# Charger.net
KiCad netlist of a schematic drawn in Altium Designer
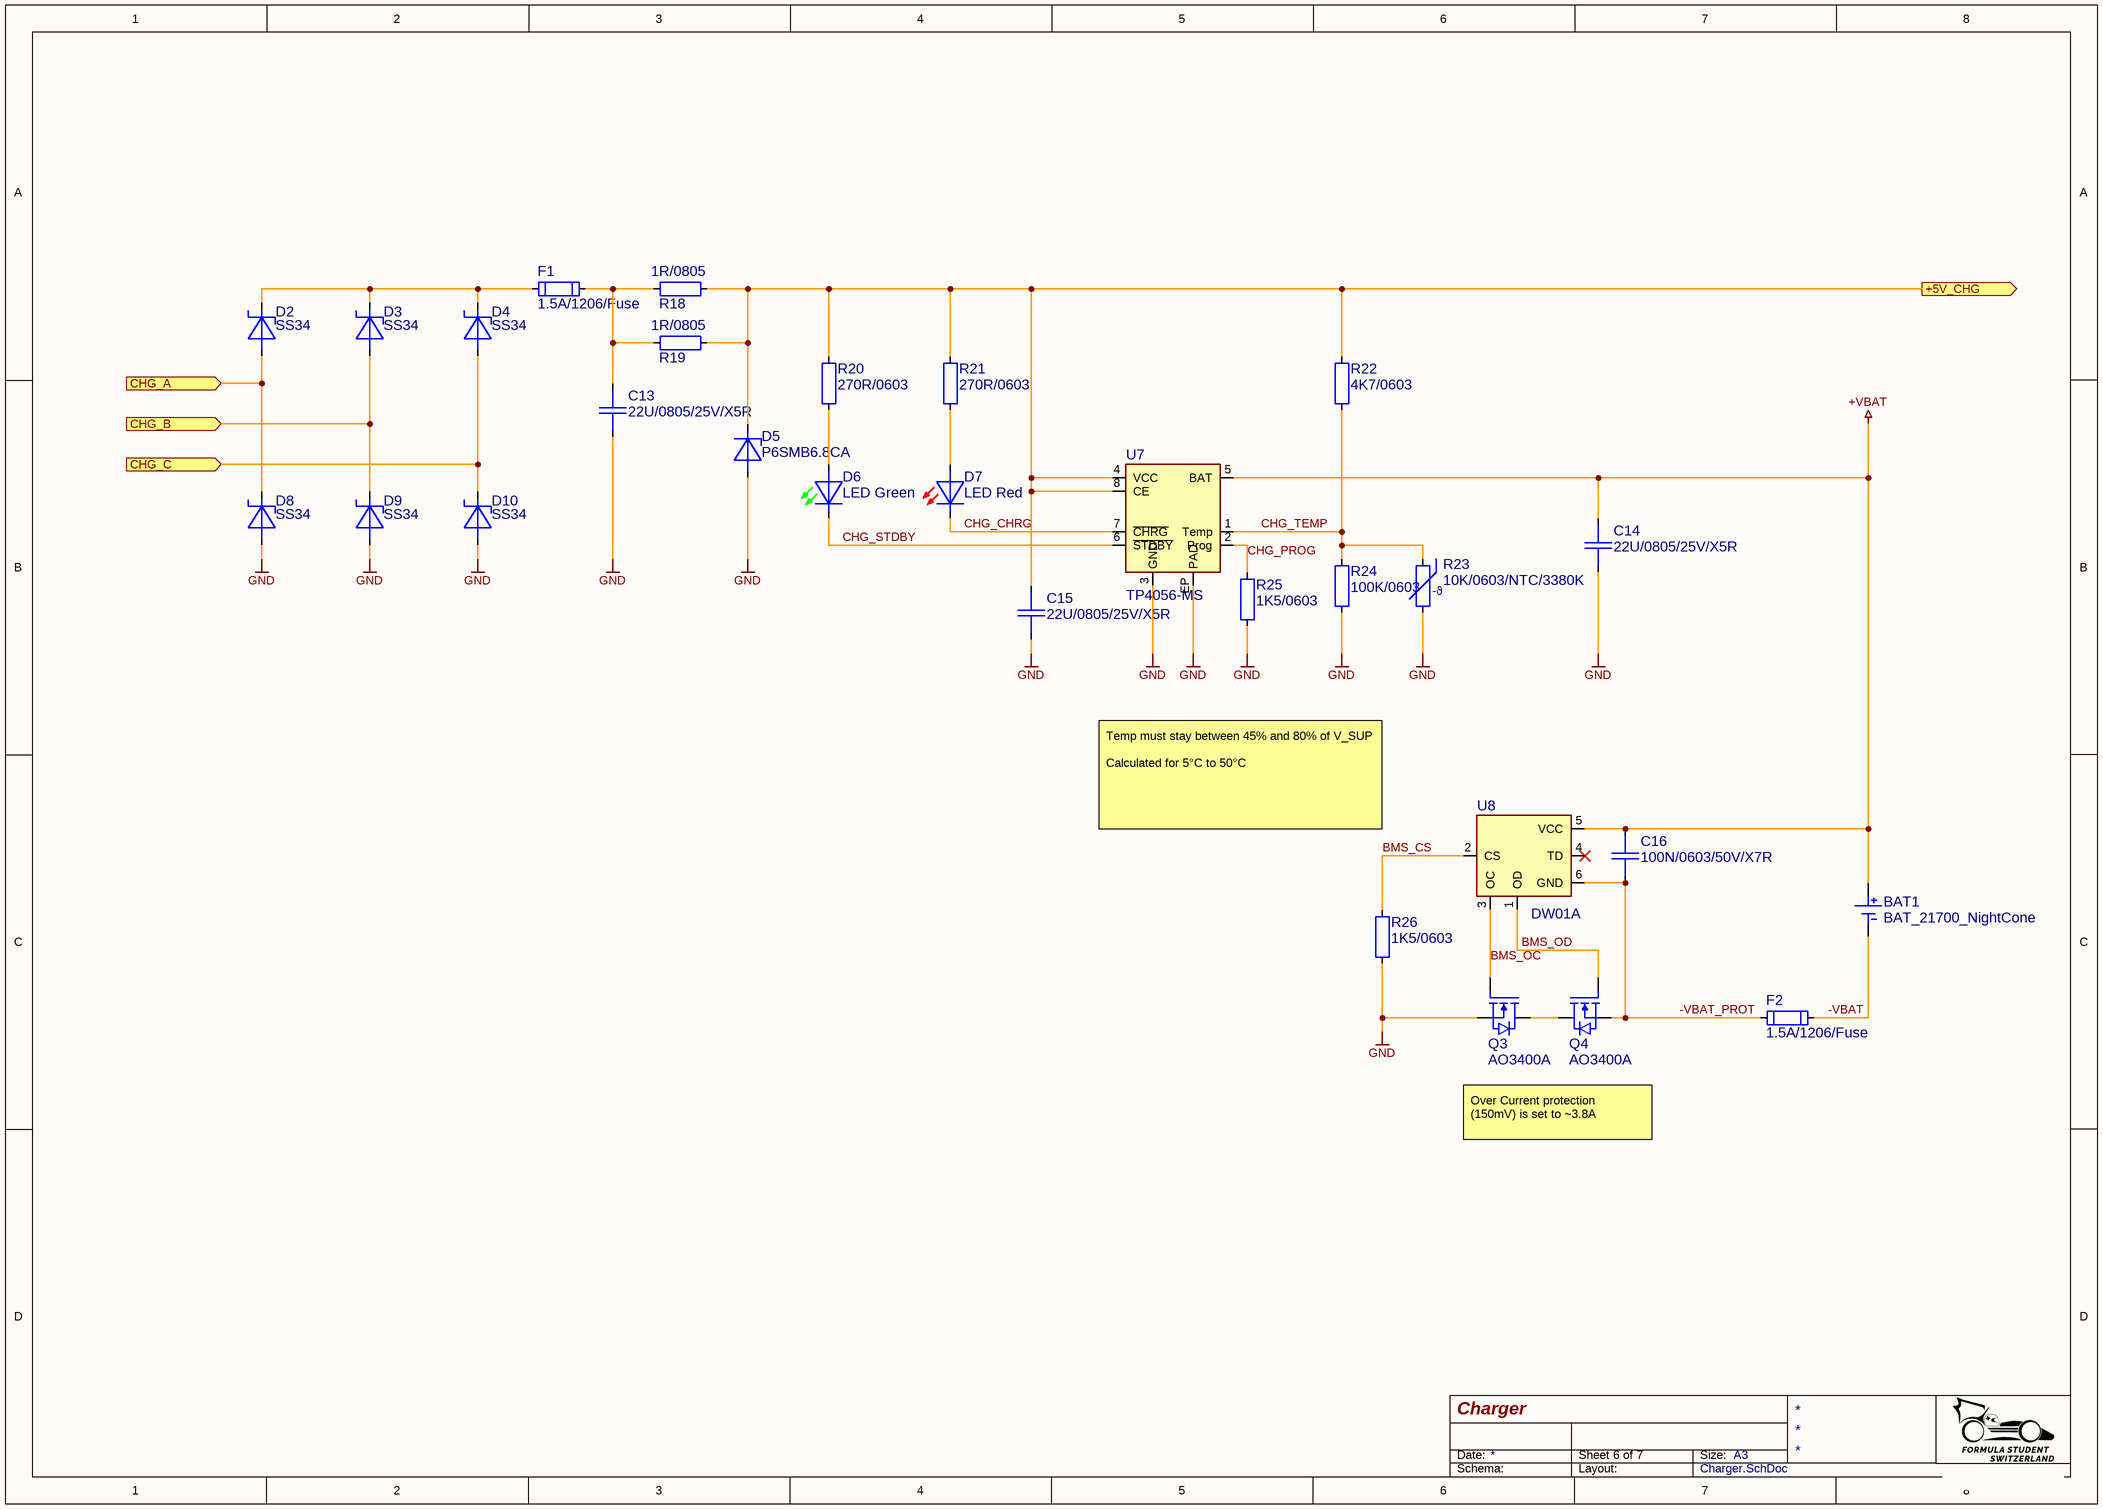
[diagram p0: Charger.SchDoc]

(export (version "E")
  (design (tool "Eeschema 10.0.6"))
  (components
    (comp (ref "BAT1")
      (value "BAT_21700_NightCone")
      (footprint "BAT-21700-NC")
      (description "21700 Battery cell for FSCH nightcone project")
      (fields (field (name "MANUFACTURER") "NONE"))
      (libsource (lib "daniw_altium_lib") (part "Battery_1"))
    )
    (comp (ref "C13")
      (value "22U/0805/25V/X5R")
      (footprint "CAP0805_X7R")
      (description "CAP SM 0805 22uF 25V X5R")
      (fields (field (name "MANUFACTURER") "GENERIC"))
      (libsource (lib "daniw_altium_lib") (part "C"))
    )
    (comp (ref "C14")
      (value "22U/0805/25V/X5R")
      (footprint "CAP0805_X7R")
      (description "CAP SM 0805 22uF 25V X5R")
      (fields (field (name "MANUFACTURER") "GENERIC"))
      (libsource (lib "daniw_altium_lib") (part "C"))
    )
    (comp (ref "C15")
      (value "22U/0805/25V/X5R")
      (footprint "CAP0805_X7R")
      (description "CAP SM 0805 22uF 25V X5R")
      (fields (field (name "MANUFACTURER") "GENERIC"))
      (libsource (lib "daniw_altium_lib") (part "C"))
    )
    (comp (ref "C16")
      (value "100N/0603/50V/X7R")
      (footprint "CAP0603_X7R")
      (description "CAP SM 0603 100nF 50V X7R")
      (fields (field (name "MANUFACTURER") "GENERIC"))
      (libsource (lib "daniw_altium_lib") (part "C"))
    )
    (comp (ref "D2")
      (value "SS34")
      (footprint "DIOM5226X230")
      (description "Si Shottky Diode 3A DO-214AC")
      (fields (field (name "MANUFACTURER") "GENERIC"))
      (libsource (lib "daniw_altium_lib") (part "D_Schottky"))
    )
    (comp (ref "D3")
      (value "SS34")
      (footprint "DIOM5226X230")
      (description "Si Shottky Diode 3A DO-214AC")
      (fields (field (name "MANUFACTURER") "GENERIC"))
      (libsource (lib "daniw_altium_lib") (part "D_Schottky"))
    )
    (comp (ref "D4")
      (value "SS34")
      (footprint "DIOM5226X230")
      (description "Si Shottky Diode 3A DO-214AC")
      (fields (field (name "MANUFACTURER") "GENERIC"))
      (libsource (lib "daniw_altium_lib") (part "D_Schottky"))
    )
    (comp (ref "D5")
      (value "P6SMB6.8CA")
      (footprint "DIOM5436X265")
      (description "10.5V 6.45V 5.8V SMB(DO-214AA) TVS")
      (fields (field (name "MANUFACTURER") "Littelfuse Inc."))
      (libsource (lib "daniw_altium_lib") (part "D_Zener"))
    )
    (comp (ref "D6")
      (value "LED Green")
      (footprint "LED0805_GREEN")
      (description "Generic LED Green 0805")
      (fields (field (name "PART NUMBER") "LED Green 0805") (field (name "MANUFACTURER") "GENERIC"))
      (libsource (lib "daniw_altium_lib") (part "LED_GREEN"))
    )
    (comp (ref "D7")
      (value "LED Red")
      (footprint "LED0805_RED")
      (description "Generic LED Red 0805")
      (fields (field (name "PART NUMBER") "LED Red 0805") (field (name "MANUFACTURER") "GENERIC"))
      (libsource (lib "daniw_altium_lib") (part "LED_RED"))
    )
    (comp (ref "D8")
      (value "SS34")
      (footprint "DIOM5226X230")
      (description "Si Shottky Diode 3A DO-214AC")
      (fields (field (name "MANUFACTURER") "GENERIC"))
      (libsource (lib "daniw_altium_lib") (part "D_Schottky"))
    )
    (comp (ref "D9")
      (value "SS34")
      (footprint "DIOM5226X230")
      (description "Si Shottky Diode 3A DO-214AC")
      (fields (field (name "MANUFACTURER") "GENERIC"))
      (libsource (lib "daniw_altium_lib") (part "D_Schottky"))
    )
    (comp (ref "D10")
      (value "SS34")
      (footprint "DIOM5226X230")
      (description "Si Shottky Diode 3A DO-214AC")
      (fields (field (name "MANUFACTURER") "GENERIC"))
      (libsource (lib "daniw_altium_lib") (part "D_Schottky"))
    )
    (comp (ref "F1")
      (value "1.5A/1206/Fuse")
      (footprint "Fuse1206-0.55-WW")
      (description "Multifuse 1206 1.5A")
      (fields (field (name "MANUFACTURER") "GENERIC"))
      (libsource (lib "daniw_altium_lib") (part "Fuse"))
    )
    (comp (ref "F2")
      (value "1.5A/1206/Fuse")
      (footprint "Fuse1206-0.55-WW")
      (description "Multifuse 1206 1.5A")
      (fields (field (name "MANUFACTURER") "GENERIC"))
      (libsource (lib "daniw_altium_lib") (part "Fuse"))
    )
    (comp (ref "Q3")
      (value "AO3400A")
      (footprint "SOT2395P280X125-3-SE")
      (description "30V N-Channel MOSFET")
      (fields (field (name "MANUFACTURER") "Alpha & Omega Semiconductor"))
      (libsource (lib "daniw_altium_lib") (part "MOSFET N_SOT23"))
    )
    (comp (ref "Q4")
      (value "AO3400A")
      (footprint "SOT2395P280X125-3-SE")
      (description "30V N-Channel MOSFET")
      (fields (field (name "MANUFACTURER") "Alpha & Omega Semiconductor"))
      (libsource (lib "daniw_altium_lib") (part "MOSFET N_SOT23"))
    )
    (comp (ref "R18")
      (value "1R/0805")
      (footprint "R0805-0.50-WW")
      (description "RES SM 0805 1R")
      (fields (field (name "MANUFACTURER") "GENERIC"))
      (libsource (lib "daniw_altium_lib") (part "R"))
    )
    (comp (ref "R19")
      (value "1R/0805")
      (footprint "R0805-0.50-WW")
      (description "RES SM 0805 1R")
      (fields (field (name "MANUFACTURER") "GENERIC"))
      (libsource (lib "daniw_altium_lib") (part "R"))
    )
    (comp (ref "R20")
      (value "270R/0603")
      (footprint "R0603-0.40-WW")
      (description "RES SM 0603 270R")
      (fields (field (name "MANUFACTURER") "GENERIC"))
      (libsource (lib "daniw_altium_lib") (part "R"))
    )
    (comp (ref "R21")
      (value "270R/0603")
      (footprint "R0603-0.40-WW")
      (description "RES SM 0603 270R")
      (fields (field (name "MANUFACTURER") "GENERIC"))
      (libsource (lib "daniw_altium_lib") (part "R"))
    )
    (comp (ref "R22")
      (value "4K7/0603")
      (footprint "R0603-0.40-WW")
      (description "RES SM 0603 4K7")
      (fields (field (name "MANUFACTURER") "GENERIC"))
      (libsource (lib "daniw_altium_lib") (part "R"))
    )
    (comp (ref "R23")
      (value "10K/0603/NTC/3380K")
      (footprint "R0603-0.40-WW")
      (description "RES NTC SM 0603 10K")
      (fields (field (name "MANUFACTURER") "GENERIC"))
      (libsource (lib "daniw_altium_lib") (part "R_NTC"))
    )
    (comp (ref "R24")
      (value "100K/0603")
      (footprint "R0603-0.40-WW")
      (description "RES SM 0603 100K")
      (fields (field (name "MANUFACTURER") "GENERIC"))
      (libsource (lib "daniw_altium_lib") (part "R"))
    )
    (comp (ref "R25")
      (value "1K5/0603")
      (footprint "R0603-0.40-WW")
      (description "RES SM 0603 1K5")
      (fields (field (name "MANUFACTURER") "GENERIC"))
      (libsource (lib "daniw_altium_lib") (part "R"))
    )
    (comp (ref "R26")
      (value "1K5/0603")
      (footprint "R0603-0.40-WW")
      (description "RES SM 0603 1K5")
      (fields (field (name "MANUFACTURER") "GENERIC"))
      (libsource (lib "daniw_altium_lib") (part "R"))
    )
    (comp (ref "U7")
      (value "TP4056-MS")
      (footprint "SOP127P600X155-9-TH330x240-NW")
      (description "1A Standalone Linear Li-lon Battery Charger with Thermal Regulation in SOP-8")
      (fields (field (name "MANUFACTURER") "MSKSEMI"))
      (libsource (lib "daniw_altium_lib") (part "TP4056"))
    )
    (comp (ref "U8")
      (value "DW01A")
      (footprint "SOT2395P280X125-6-SW")
      (description "Single Cell Lithium-ion battery protection IC")
      (fields (field (name "MANUFACTURER") "PUOLOP"))
      (libsource (lib "daniw_altium_lib") (part "DW01A"))
    )
  )
  (nets
    (net (code "1") (name "+VBAT") (class "Default")
      (node (ref "BAT1") (pin "1") (pinfunction "+_1") (pintype "passive"))
      (node (ref "C14") (pin "1") (pinfunction "1_1") (pintype "passive"))
      (node (ref "C16") (pin "1") (pinfunction "1_1") (pintype "passive"))
      (node (ref "U7") (pin "5") (pinfunction "BAT_5") (pintype "passive"))
      (node (ref "U8") (pin "5") (pinfunction "VCC_5") (pintype "passive"))
    )
    (net (code "2") (name "/+5V_CHG") (class "Default")
      (node (ref "C15") (pin "1") (pinfunction "1_1") (pintype "passive"))
      (node (ref "D5") (pin "1") (pinfunction "1_1") (pintype "passive"))
      (node (ref "R18") (pin "2") (pinfunction "2_2") (pintype "passive"))
      (node (ref "R19") (pin "2") (pinfunction "2_2") (pintype "passive"))
      (node (ref "R20") (pin "1") (pinfunction "1_1") (pintype "passive"))
      (node (ref "R21") (pin "1") (pinfunction "1_1") (pintype "passive"))
      (node (ref "R22") (pin "1") (pinfunction "1_1") (pintype "passive"))
      (node (ref "U7") (pin "4") (pinfunction "VCC_4") (pintype "passive"))
      (node (ref "U7") (pin "8") (pinfunction "CE_8") (pintype "passive"))
    )
    (net (code "3") (name "/-VBAT") (class "Default")
      (node (ref "BAT1") (pin "2") (pinfunction "-_2") (pintype "passive"))
      (node (ref "F2") (pin "1") (pinfunction "1_1") (pintype "passive"))
    )
    (net (code "4") (name "/-VBAT_PROT") (class "Default")
      (node (ref "C16") (pin "2") (pinfunction "2_2") (pintype "passive"))
      (node (ref "F2") (pin "2") (pinfunction "2_2") (pintype "passive"))
      (node (ref "Q4") (pin "2") (pinfunction "SOURCE_2") (pintype "passive"))
      (node (ref "U8") (pin "6") (pinfunction "GND_6") (pintype "passive"))
    )
    (net (code "5") (name "/BMS_CS") (class "Default")
      (node (ref "R26") (pin "1") (pinfunction "1_1") (pintype "passive"))
      (node (ref "U8") (pin "2") (pinfunction "CS_2") (pintype "passive"))
    )
    (net (code "6") (name "/BMS_OC") (class "Default")
      (node (ref "Q3") (pin "1") (pinfunction "GATE_1") (pintype "passive"))
      (node (ref "U8") (pin "3") (pinfunction "OC_3") (pintype "passive"))
    )
    (net (code "7") (name "/BMS_OD") (class "Default")
      (node (ref "Q4") (pin "1") (pinfunction "GATE_1") (pintype "passive"))
      (node (ref "U8") (pin "1") (pinfunction "OD_1") (pintype "passive"))
    )
    (net (code "8") (name "/CHG_A") (class "Default")
      (node (ref "D2") (pin "2") (pinfunction "2_2") (pintype "passive"))
      (node (ref "D8") (pin "1") (pinfunction "1_1") (pintype "passive"))
    )
    (net (code "9") (name "/CHG_B") (class "Default")
      (node (ref "D3") (pin "2") (pinfunction "2_2") (pintype "passive"))
      (node (ref "D9") (pin "1") (pinfunction "1_1") (pintype "passive"))
    )
    (net (code "10") (name "/CHG_C") (class "Default")
      (node (ref "D10") (pin "1") (pinfunction "1_1") (pintype "passive"))
      (node (ref "D4") (pin "2") (pinfunction "2_2") (pintype "passive"))
    )
    (net (code "11") (name "/CHG_CHRG") (class "Default")
      (node (ref "D7") (pin "1") (pinfunction "1_1") (pintype "passive"))
      (node (ref "U7") (pin "7") (pinfunction "~{CHRG}_7") (pintype "passive"))
    )
    (net (code "12") (name "/CHG_PROG") (class "Default")
      (node (ref "R25") (pin "1") (pinfunction "1_1") (pintype "passive"))
      (node (ref "U7") (pin "2") (pinfunction "Prog_2") (pintype "passive"))
    )
    (net (code "13") (name "/CHG_STDBY") (class "Default")
      (node (ref "D6") (pin "1") (pinfunction "1_1") (pintype "passive"))
      (node (ref "U7") (pin "6") (pinfunction "~{STDBY}_6") (pintype "passive"))
    )
    (net (code "14") (name "/CHG_TEMP") (class "Default")
      (node (ref "R22") (pin "2") (pinfunction "2_2") (pintype "passive"))
      (node (ref "R23") (pin "1") (pinfunction "1_1") (pintype "passive"))
      (node (ref "R24") (pin "1") (pinfunction "1_1") (pintype "passive"))
      (node (ref "U7") (pin "1") (pinfunction "Temp_1") (pintype "passive"))
    )
    (net (code "15") (name "GND") (class "Default")
      (node (ref "C13") (pin "2") (pinfunction "2_2") (pintype "passive"))
      (node (ref "C14") (pin "2") (pinfunction "2_2") (pintype "passive"))
      (node (ref "C15") (pin "2") (pinfunction "2_2") (pintype "passive"))
      (node (ref "D10") (pin "2") (pinfunction "2_2") (pintype "passive"))
      (node (ref "D5") (pin "2") (pinfunction "2_2") (pintype "passive"))
      (node (ref "D8") (pin "2") (pinfunction "2_2") (pintype "passive"))
      (node (ref "D9") (pin "2") (pinfunction "2_2") (pintype "passive"))
      (node (ref "Q3") (pin "2") (pinfunction "SOURCE_2") (pintype "passive"))
      (node (ref "R23") (pin "2") (pinfunction "2_2") (pintype "passive"))
      (node (ref "R24") (pin "2") (pinfunction "2_2") (pintype "passive"))
      (node (ref "R25") (pin "2") (pinfunction "2_2") (pintype "passive"))
      (node (ref "R26") (pin "2") (pinfunction "2_2") (pintype "passive"))
      (node (ref "U7") (pin "3") (pinfunction "GND_3") (pintype "passive"))
      (node (ref "U7") (pin "EP") (pinfunction "PAD_EP") (pintype "passive"))
    )
    (net (code "16") (name "Net-(C13-Pad1)") (class "Default")
      (node (ref "C13") (pin "1") (pinfunction "1_1") (pintype "passive"))
      (node (ref "F1") (pin "2") (pinfunction "2_2") (pintype "passive"))
      (node (ref "R18") (pin "1") (pinfunction "1_1") (pintype "passive"))
      (node (ref "R19") (pin "1") (pinfunction "1_1") (pintype "passive"))
    )
    (net (code "17") (name "Net-(D2-Pad1)") (class "Default")
      (node (ref "D2") (pin "1") (pinfunction "1_1") (pintype "passive"))
      (node (ref "D3") (pin "1") (pinfunction "1_1") (pintype "passive"))
      (node (ref "D4") (pin "1") (pinfunction "1_1") (pintype "passive"))
      (node (ref "F1") (pin "1") (pinfunction "1_1") (pintype "passive"))
    )
    (net (code "18") (name "Net-(D6-Pad2)") (class "Default")
      (node (ref "D6") (pin "2") (pinfunction "2_2") (pintype "passive"))
      (node (ref "R20") (pin "2") (pinfunction "2_2") (pintype "passive"))
    )
    (net (code "19") (name "Net-(D7-Pad2)") (class "Default")
      (node (ref "D7") (pin "2") (pinfunction "2_2") (pintype "passive"))
      (node (ref "R21") (pin "2") (pinfunction "2_2") (pintype "passive"))
    )
    (net (code "20") (name "Net-(Q3-DRAIN)") (class "Default")
      (node (ref "Q3") (pin "3") (pinfunction "DRAIN_3") (pintype "passive"))
      (node (ref "Q4") (pin "3") (pinfunction "DRAIN_3") (pintype "passive"))
    )
    (net (code "21") (name "unconnected-(U8-TD-Pad4)") (class "Default")
      (node (ref "U8") (pin "4") (pinfunction "TD_4") (pintype "passive+no_connect"))
    )
  )
)
